# sensors.net
KiCad netlist of a schematic drawn in Altium Designer
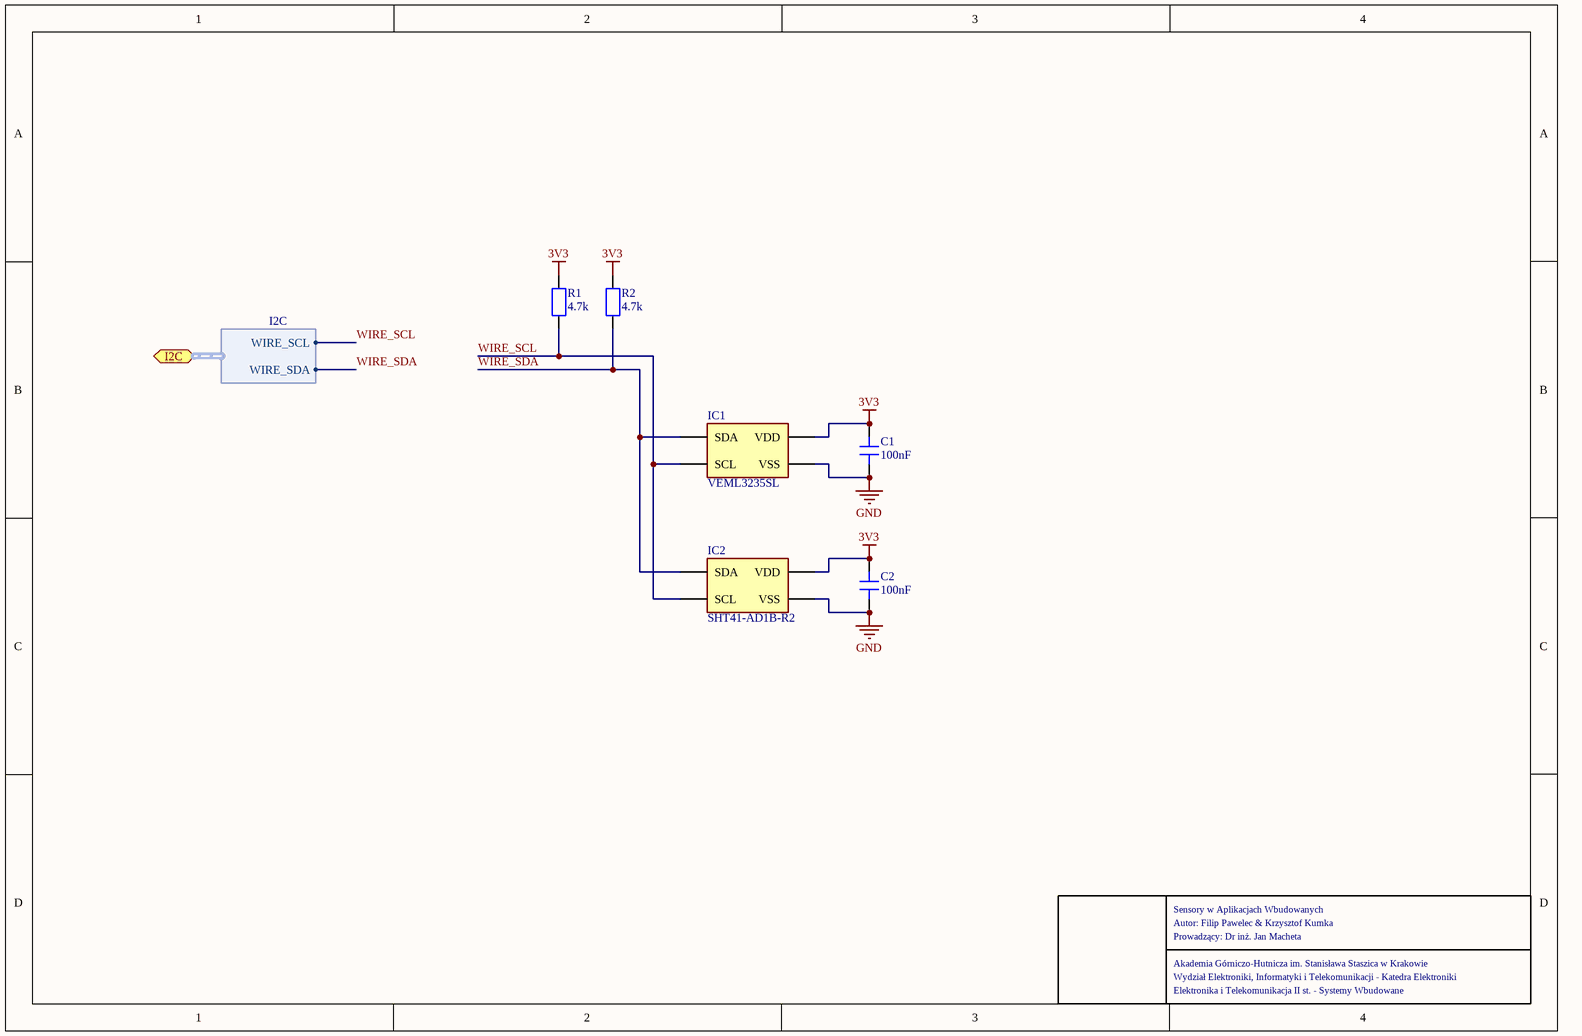
[diagram p0: sensors.SchDoc]

(export (version "E")
  (design (tool "Eeschema 10.0.6"))
  (components
    (comp (ref "C1")
      (value "100nF")
      (footprint "C0603")
      (description "Capacitor")
      (libsource (lib "TEMD_lib") (part "C0603"))
    )
    (comp (ref "C2")
      (value "100nF")
      (footprint "C0603")
      (description "Capacitor")
      (libsource (lib "TEMD_lib") (part "C0603"))
    )
    (comp (ref "IC1")
      (value "VEML3235SL")
      (footprint "VEML3235SL")
      (description "Integrated Circuit")
      (libsource (lib "embSensAppLib") (part "VEML3235SL"))
    )
    (comp (ref "IC2")
      (value "SHT41-AD1B-R2")
      (footprint "SHT41AD1BR2")
      (description "Integrated Circuit")
      (libsource (lib "TEMD_lib") (part "SHT41-AD1B-R2"))
    )
    (comp (ref "R1")
      (value "4.7k")
      (footprint "R0603")
      (description "Resistor")
      (libsource (lib "embSensAppLib") (part "R0603"))
    )
    (comp (ref "R2")
      (value "4.7k")
      (footprint "R0603")
      (description "Resistor")
      (libsource (lib "embSensAppLib") (part "R0603"))
    )
  )
  (nets
    (net (code "2") (name "/WIRE_SCL") (class "Default")
      (node (ref "IC1") (pin "4") (pinfunction "SCL_4") (pintype "passive"))
      (node (ref "IC2") (pin "2") (pinfunction "SCL_2") (pintype "passive"))
      (node (ref "R1") (pin "1") (pinfunction "1_1") (pintype "passive"))
    )
    (net (code "3") (name "/WIRE_SDA") (class "Default")
      (node (ref "IC1") (pin "3") (pinfunction "SDA_3") (pintype "passive"))
      (node (ref "IC2") (pin "1") (pinfunction "SDA_1") (pintype "passive"))
      (node (ref "R2") (pin "1") (pinfunction "1_1") (pintype "passive"))
    )
    (net (code "5") (name "3V3") (class "Default")
      (node (ref "C1") (pin "2") (pinfunction "2_2") (pintype "passive"))
      (node (ref "C2") (pin "2") (pinfunction "2_2") (pintype "passive"))
      (node (ref "IC1") (pin "1") (pinfunction "VDD_1") (pintype "passive"))
      (node (ref "IC2") (pin "3") (pinfunction "VDD_3") (pintype "passive"))
      (node (ref "R1") (pin "2") (pinfunction "2_2") (pintype "passive"))
      (node (ref "R2") (pin "2") (pinfunction "2_2") (pintype "passive"))
    )
    (net (code "6") (name "GND") (class "Default")
      (node (ref "C1") (pin "1") (pinfunction "1_1") (pintype "passive"))
      (node (ref "C2") (pin "1") (pinfunction "1_1") (pintype "passive"))
      (node (ref "IC1") (pin "2") (pinfunction "VSS_2") (pintype "passive"))
      (node (ref "IC2") (pin "4") (pinfunction "VSS_4") (pintype "passive"))
    )
  )
)
